# CNC_v36.net
KiCad netlist of a schematic drawn in EAGLE
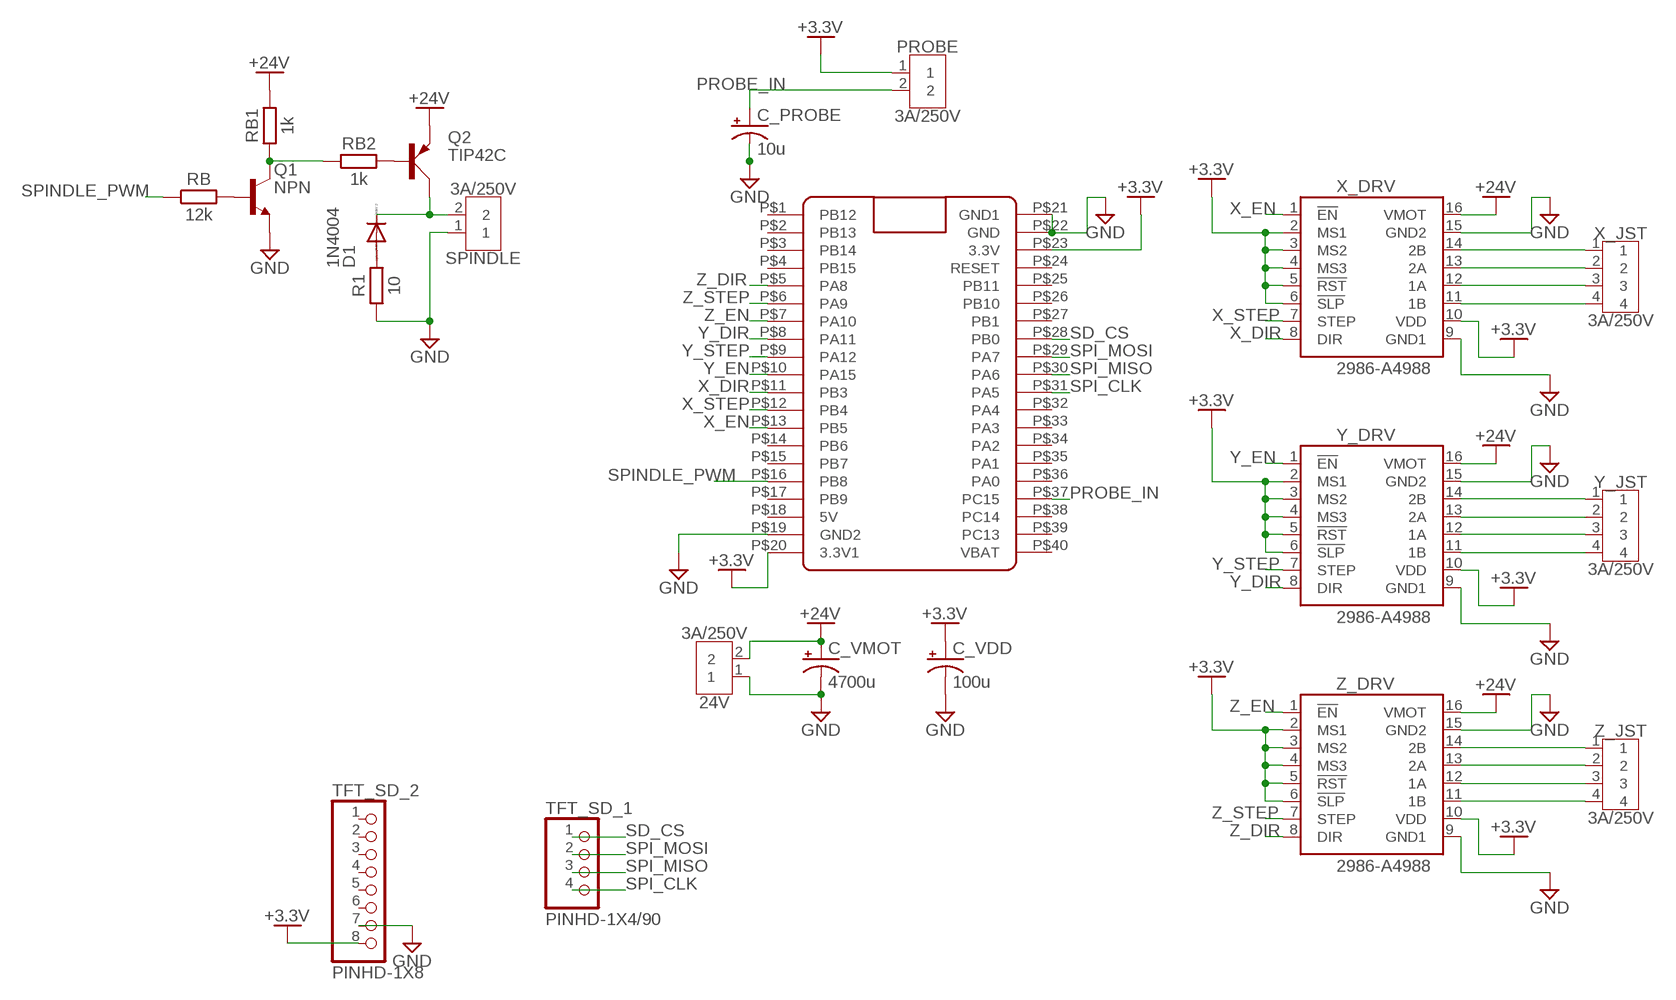
[diagram p0: schematic, sheet 1]

(export (version "E")
  (design (tool "Eeschema 10.0.6"))
  (components
    (comp (ref "24V")
      (value "3A/250V")
      (footprint "eagle-import:B2B-XH-A")
      (fields (field (name "MANUFACTURER") "JST (XH CONNECTOR)") (field (name "MPN") "B2B-XH-A"))
      (libsource (lib "eagle-import") (part "B2B-XH-A"))
    )
    (comp (ref "C_PROBE")
      (value "10u")
      (footprint "eagle-import:CAPPRD508W65D1000H1100B")
      (libsource (lib "eagle-import") (part "C-POL-USRADIAL-11MM-DIA_"))
    )
    (comp (ref "C_VDD")
      (value "100u")
      (footprint "eagle-import:CAPPRD508W65D1000H1100B")
      (libsource (lib "eagle-import") (part "C-POL-USRADIAL-11MM-DIA_"))
    )
    (comp (ref "C_VMOT")
      (value "4700u")
      (footprint "eagle-import:CAPPRD550W60D1200H2000B")
      (libsource (lib "eagle-import") (part "C-POL-USRADIAL-20MM-DIA_"))
    )
    (comp (ref "D1")
      (value "1N4004")
      (footprint "eagle-import:DO41-10")
      (libsource (lib "eagle-import") (part "1N4004"))
    )
    (comp (ref "PROBE")
      (value "3A/250V")
      (footprint "eagle-import:B2B-XH-A")
      (fields (field (name "MANUFACTURER") "JST (XH CONNECTOR)") (field (name "MPN") "B2B-XH-A"))
      (libsource (lib "eagle-import") (part "B2B-XH-A"))
    )
    (comp (ref "Q1")
      (value "NPN")
      (footprint "eagle-import:TO92")
      (libsource (lib "eagle-import") (part "NPNTO92-EBC_"))
    )
    (comp (ref "Q2")
      (value "TIP42C")
      (footprint "eagle-import:TO220AV")
      (fields (field (name "MF") "onsemi"))
      (libsource (lib "eagle-import") (part "TIP42C"))
    )
    (comp (ref "R1")
      (value "10")
      (footprint "eagle-import:RESAD724W46L381D178B")
      (libsource (lib "eagle-import") (part "RAXIAL-7.2MM-PITCH_"))
    )
    (comp (ref "RB")
      (value "12k")
      (footprint "eagle-import:RESAD724W46L381D178B")
      (libsource (lib "eagle-import") (part "RAXIAL-7.2MM-PITCH_"))
    )
    (comp (ref "RB1")
      (value "1k")
      (footprint "eagle-import:RESAD724W46L381D178B")
      (libsource (lib "eagle-import") (part "RAXIAL-7.2MM-PITCH_"))
    )
    (comp (ref "RB2")
      (value "1k")
      (footprint "eagle-import:RESAD724W46L381D178B")
      (libsource (lib "eagle-import") (part "RAXIAL-7.2MM-PITCH_"))
    )
    (comp (ref "SPINDLE")
      (value "3A/250V")
      (footprint "eagle-import:B2B-XH-A")
      (fields (field (name "MANUFACTURER") "JST (XH CONNECTOR)") (field (name "MPN") "B2B-XH-A"))
      (libsource (lib "eagle-import") (part "B2B-XH-A"))
    )
    (comp (ref "TFT_SD_1")
      (value "PINHD-1X4/90")
      (footprint "eagle-import:1X04_90")
      (libsource (lib "eagle-import") (part "PINHD-1X4/90"))
    )
    (comp (ref "TFT_SD_2")
      (value "PINHD-1X8")
      (footprint "eagle-import:1X08")
      (libsource (lib "eagle-import") (part "PINHD-1X8"))
    )
    (comp (ref "U$1")
      (value "BLUE_PILLADVANCED")
      (footprint "eagle-import:BLUE_PILL_ADV")
      (libsource (lib "eagle-import") (part "BLUE_PILLADVANCED"))
    )
    (comp (ref "X_DRV")
      (value "2986-A4988")
      (footprint "eagle-import:A4988")
      (libsource (lib "eagle-import") (part "2986-A4988"))
    )
    (comp (ref "X_JST")
      (value "3A/250V")
      (footprint "eagle-import:B4B-XH-A")
      (fields (field (name "MANUFACTURER") "JST (XH connector)") (field (name "MPN") "B4B-XH-A"))
      (libsource (lib "eagle-import") (part "B4B-XH-A"))
    )
    (comp (ref "Y_DRV")
      (value "2986-A4988")
      (footprint "eagle-import:A4988")
      (libsource (lib "eagle-import") (part "2986-A4988"))
    )
    (comp (ref "Y_JST")
      (value "3A/250V")
      (footprint "eagle-import:B4B-XH-A")
      (fields (field (name "MANUFACTURER") "JST (XH connector)") (field (name "MPN") "B4B-XH-A"))
      (libsource (lib "eagle-import") (part "B4B-XH-A"))
    )
    (comp (ref "Z_DRV")
      (value "2986-A4988")
      (footprint "eagle-import:A4988")
      (libsource (lib "eagle-import") (part "2986-A4988"))
    )
    (comp (ref "Z_JST")
      (value "3A/250V")
      (footprint "eagle-import:B4B-XH-A")
      (fields (field (name "MANUFACTURER") "JST (XH connector)") (field (name "MPN") "B4B-XH-A"))
      (libsource (lib "eagle-import") (part "B4B-XH-A"))
    )
  )
  (nets
    (net (code "1") (name "+3.3V") (class "Default")
      (node (ref "C_VDD") (pin "1") (pinfunction "+_1") (pintype "passive"))
      (node (ref "PROBE") (pin "1") (pinfunction "1_1") (pintype "bidirectional"))
      (node (ref "TFT_SD_2") (pin "8") (pinfunction "8_8") (pintype "passive"))
      (node (ref "U$1") (pin "P$20") (pinfunction "3.3V1_P$20") (pintype "bidirectional"))
      (node (ref "U$1") (pin "P$23") (pinfunction "3.3V_P$23") (pintype "bidirectional"))
      (node (ref "X_DRV") (pin "10") (pinfunction "VDD_10") (pintype "power_in"))
      (node (ref "X_DRV") (pin "2") (pinfunction "MS1_2") (pintype "passive"))
      (node (ref "X_DRV") (pin "3") (pinfunction "MS2_3") (pintype "passive"))
      (node (ref "X_DRV") (pin "4") (pinfunction "MS3_4") (pintype "passive"))
      (node (ref "X_DRV") (pin "5") (pinfunction "~{RST}_5") (pintype "passive"))
      (node (ref "X_DRV") (pin "6") (pinfunction "~{SLP}_6") (pintype "passive"))
      (node (ref "Y_DRV") (pin "10") (pinfunction "VDD_10") (pintype "power_in"))
      (node (ref "Y_DRV") (pin "2") (pinfunction "MS1_2") (pintype "passive"))
      (node (ref "Y_DRV") (pin "3") (pinfunction "MS2_3") (pintype "passive"))
      (node (ref "Y_DRV") (pin "4") (pinfunction "MS3_4") (pintype "passive"))
      (node (ref "Y_DRV") (pin "5") (pinfunction "~{RST}_5") (pintype "passive"))
      (node (ref "Y_DRV") (pin "6") (pinfunction "~{SLP}_6") (pintype "passive"))
      (node (ref "Z_DRV") (pin "10") (pinfunction "VDD_10") (pintype "power_in"))
      (node (ref "Z_DRV") (pin "2") (pinfunction "MS1_2") (pintype "passive"))
      (node (ref "Z_DRV") (pin "3") (pinfunction "MS2_3") (pintype "passive"))
      (node (ref "Z_DRV") (pin "4") (pinfunction "MS3_4") (pintype "passive"))
      (node (ref "Z_DRV") (pin "5") (pinfunction "~{RST}_5") (pintype "passive"))
      (node (ref "Z_DRV") (pin "6") (pinfunction "~{SLP}_6") (pintype "passive"))
    )
    (net (code "2") (name "+24V") (class "Default")
      (node (ref "24V") (pin "2") (pinfunction "2_2") (pintype "bidirectional"))
      (node (ref "C_VMOT") (pin "1") (pinfunction "+_1") (pintype "passive"))
      (node (ref "Q2") (pin "E") (pinfunction "E_E") (pintype "passive"))
      (node (ref "RB1") (pin "2") (pinfunction "2_2") (pintype "passive"))
      (node (ref "X_DRV") (pin "16") (pinfunction "VMOT_16") (pintype "power_in"))
      (node (ref "Y_DRV") (pin "16") (pinfunction "VMOT_16") (pintype "power_in"))
      (node (ref "Z_DRV") (pin "16") (pinfunction "VMOT_16") (pintype "power_in"))
    )
    (net (code "3") (name "/PROBE_IN") (class "Default")
      (node (ref "C_PROBE") (pin "1") (pinfunction "+_1") (pintype "passive"))
      (node (ref "PROBE") (pin "2") (pinfunction "2_2") (pintype "bidirectional"))
      (node (ref "U$1") (pin "P$37") (pinfunction "PC15_P$37") (pintype "bidirectional"))
    )
    (net (code "4") (name "/SD_CS") (class "Default")
      (node (ref "TFT_SD_1") (pin "1") (pinfunction "1_1") (pintype "passive"))
      (node (ref "U$1") (pin "P$28") (pinfunction "PB0_P$28") (pintype "bidirectional"))
    )
    (net (code "5") (name "/SPINDLE_PWM") (class "Default")
      (node (ref "RB") (pin "1") (pinfunction "1_1") (pintype "passive"))
      (node (ref "U$1") (pin "P$16") (pinfunction "PB8_P$16") (pintype "bidirectional"))
    )
    (net (code "6") (name "/SPI_CLK") (class "Default")
      (node (ref "TFT_SD_1") (pin "4") (pinfunction "4_4") (pintype "passive"))
      (node (ref "U$1") (pin "P$31") (pinfunction "PA5_P$31") (pintype "bidirectional"))
    )
    (net (code "7") (name "/SPI_MISO") (class "Default")
      (node (ref "TFT_SD_1") (pin "3") (pinfunction "3_3") (pintype "passive"))
      (node (ref "U$1") (pin "P$30") (pinfunction "PA6_P$30") (pintype "bidirectional"))
    )
    (net (code "8") (name "/SPI_MOSI") (class "Default")
      (node (ref "TFT_SD_1") (pin "2") (pinfunction "2_2") (pintype "passive"))
      (node (ref "U$1") (pin "P$29") (pinfunction "PA7_P$29") (pintype "bidirectional"))
    )
    (net (code "9") (name "/X_DIR") (class "Default")
      (node (ref "U$1") (pin "P$11") (pinfunction "PB3_P$11") (pintype "bidirectional"))
      (node (ref "X_DRV") (pin "8") (pinfunction "DIR_8") (pintype "input"))
    )
    (net (code "10") (name "/X_EN") (class "Default")
      (node (ref "U$1") (pin "P$13") (pinfunction "PB5_P$13") (pintype "bidirectional"))
      (node (ref "X_DRV") (pin "1") (pinfunction "~{EN}_1") (pintype "passive"))
    )
    (net (code "11") (name "/X_STEP") (class "Default")
      (node (ref "U$1") (pin "P$12") (pinfunction "PB4_P$12") (pintype "bidirectional"))
      (node (ref "X_DRV") (pin "7") (pinfunction "STEP_7") (pintype "input"))
    )
    (net (code "12") (name "/Y_DIR") (class "Default")
      (node (ref "U$1") (pin "P$8") (pinfunction "PA11_P$8") (pintype "bidirectional"))
      (node (ref "Y_DRV") (pin "8") (pinfunction "DIR_8") (pintype "input"))
    )
    (net (code "13") (name "/Y_EN") (class "Default")
      (node (ref "U$1") (pin "P$10") (pinfunction "PA15_P$10") (pintype "bidirectional"))
      (node (ref "Y_DRV") (pin "1") (pinfunction "~{EN}_1") (pintype "passive"))
    )
    (net (code "14") (name "/Y_STEP") (class "Default")
      (node (ref "U$1") (pin "P$9") (pinfunction "PA12_P$9") (pintype "bidirectional"))
      (node (ref "Y_DRV") (pin "7") (pinfunction "STEP_7") (pintype "input"))
    )
    (net (code "15") (name "/Z_DIR") (class "Default")
      (node (ref "U$1") (pin "P$5") (pinfunction "PA8_P$5") (pintype "bidirectional"))
      (node (ref "Z_DRV") (pin "8") (pinfunction "DIR_8") (pintype "input"))
    )
    (net (code "16") (name "/Z_EN") (class "Default")
      (node (ref "U$1") (pin "P$7") (pinfunction "PA10_P$7") (pintype "bidirectional"))
      (node (ref "Z_DRV") (pin "1") (pinfunction "~{EN}_1") (pintype "passive"))
    )
    (net (code "17") (name "/Z_STEP") (class "Default")
      (node (ref "U$1") (pin "P$6") (pinfunction "PA9_P$6") (pintype "bidirectional"))
      (node (ref "Z_DRV") (pin "7") (pinfunction "STEP_7") (pintype "input"))
    )
    (net (code "18") (name "GND") (class "Default")
      (node (ref "24V") (pin "1") (pinfunction "1_1") (pintype "bidirectional"))
      (node (ref "C_PROBE") (pin "2") (pinfunction "-_2") (pintype "passive"))
      (node (ref "C_VDD") (pin "2") (pinfunction "-_2") (pintype "passive"))
      (node (ref "C_VMOT") (pin "2") (pinfunction "-_2") (pintype "passive"))
      (node (ref "Q1") (pin "1") (pinfunction "E_1") (pintype "passive"))
      (node (ref "R1") (pin "1") (pinfunction "1_1") (pintype "passive"))
      (node (ref "SPINDLE") (pin "1") (pinfunction "1_1") (pintype "bidirectional"))
      (node (ref "TFT_SD_2") (pin "7") (pinfunction "7_7") (pintype "passive"))
      (node (ref "U$1") (pin "P$19") (pinfunction "GND2_P$19") (pintype "bidirectional"))
      (node (ref "U$1") (pin "P$21") (pinfunction "GND1_P$21") (pintype "power_in"))
      (node (ref "U$1") (pin "P$22") (pinfunction "GND_P$22") (pintype "bidirectional"))
      (node (ref "X_DRV") (pin "15") (pinfunction "GND2_15") (pintype "power_in"))
      (node (ref "X_DRV") (pin "9") (pinfunction "GND1_9") (pintype "power_in"))
      (node (ref "Y_DRV") (pin "15") (pinfunction "GND2_15") (pintype "power_in"))
      (node (ref "Y_DRV") (pin "9") (pinfunction "GND1_9") (pintype "power_in"))
      (node (ref "Z_DRV") (pin "15") (pinfunction "GND2_15") (pintype "power_in"))
      (node (ref "Z_DRV") (pin "9") (pinfunction "GND1_9") (pintype "power_in"))
    )
    (net (code "19") (name "Net-(D1-PadA)") (class "Default")
      (node (ref "D1") (pin "A") (pinfunction "A_A") (pintype "passive"))
      (node (ref "R1") (pin "2") (pinfunction "2_2") (pintype "passive"))
    )
    (net (code "20") (name "Net-(D1-PadC)") (class "Default")
      (node (ref "D1") (pin "C") (pinfunction "C_C") (pintype "passive"))
      (node (ref "Q2") (pin "C") (pinfunction "C_C") (pintype "passive"))
      (node (ref "SPINDLE") (pin "2") (pinfunction "2_2") (pintype "bidirectional"))
    )
    (net (code "21") (name "Net-(Q1-B)") (class "Default")
      (node (ref "Q1") (pin "2") (pinfunction "B_2") (pintype "passive"))
      (node (ref "RB") (pin "2") (pinfunction "2_2") (pintype "passive"))
    )
    (net (code "22") (name "Net-(Q1-C)") (class "Default")
      (node (ref "Q1") (pin "3") (pinfunction "C_3") (pintype "passive"))
      (node (ref "RB1") (pin "1") (pinfunction "1_1") (pintype "passive"))
      (node (ref "RB2") (pin "1") (pinfunction "1_1") (pintype "passive"))
    )
    (net (code "23") (name "Net-(Q2-PadB)") (class "Default")
      (node (ref "Q2") (pin "B") (pinfunction "B_B") (pintype "passive"))
      (node (ref "RB2") (pin "2") (pinfunction "2_2") (pintype "passive"))
    )
    (net (code "24") (name "Net-(X_DRV-1A)") (class "Default")
      (node (ref "X_DRV") (pin "12") (pinfunction "1A_12") (pintype "output"))
      (node (ref "X_JST") (pin "3") (pinfunction "3_3") (pintype "bidirectional"))
    )
    (net (code "25") (name "Net-(X_DRV-1B)") (class "Default")
      (node (ref "X_DRV") (pin "11") (pinfunction "1B_11") (pintype "output"))
      (node (ref "X_JST") (pin "4") (pinfunction "4_4") (pintype "bidirectional"))
    )
    (net (code "26") (name "Net-(X_DRV-2A)") (class "Default")
      (node (ref "X_DRV") (pin "13") (pinfunction "2A_13") (pintype "output"))
      (node (ref "X_JST") (pin "2") (pinfunction "2_2") (pintype "bidirectional"))
    )
    (net (code "27") (name "Net-(X_DRV-2B)") (class "Default")
      (node (ref "X_DRV") (pin "14") (pinfunction "2B_14") (pintype "output"))
      (node (ref "X_JST") (pin "1") (pinfunction "1_1") (pintype "bidirectional"))
    )
    (net (code "28") (name "Net-(Y_DRV-1A)") (class "Default")
      (node (ref "Y_DRV") (pin "12") (pinfunction "1A_12") (pintype "output"))
      (node (ref "Y_JST") (pin "3") (pinfunction "3_3") (pintype "bidirectional"))
    )
    (net (code "29") (name "Net-(Y_DRV-1B)") (class "Default")
      (node (ref "Y_DRV") (pin "11") (pinfunction "1B_11") (pintype "output"))
      (node (ref "Y_JST") (pin "4") (pinfunction "4_4") (pintype "bidirectional"))
    )
    (net (code "30") (name "Net-(Y_DRV-2A)") (class "Default")
      (node (ref "Y_DRV") (pin "13") (pinfunction "2A_13") (pintype "output"))
      (node (ref "Y_JST") (pin "2") (pinfunction "2_2") (pintype "bidirectional"))
    )
    (net (code "31") (name "Net-(Y_DRV-2B)") (class "Default")
      (node (ref "Y_DRV") (pin "14") (pinfunction "2B_14") (pintype "output"))
      (node (ref "Y_JST") (pin "1") (pinfunction "1_1") (pintype "bidirectional"))
    )
    (net (code "32") (name "Net-(Z_DRV-1A)") (class "Default")
      (node (ref "Z_DRV") (pin "12") (pinfunction "1A_12") (pintype "output"))
      (node (ref "Z_JST") (pin "3") (pinfunction "3_3") (pintype "bidirectional"))
    )
    (net (code "33") (name "Net-(Z_DRV-1B)") (class "Default")
      (node (ref "Z_DRV") (pin "11") (pinfunction "1B_11") (pintype "output"))
      (node (ref "Z_JST") (pin "4") (pinfunction "4_4") (pintype "bidirectional"))
    )
    (net (code "34") (name "Net-(Z_DRV-2A)") (class "Default")
      (node (ref "Z_DRV") (pin "13") (pinfunction "2A_13") (pintype "output"))
      (node (ref "Z_JST") (pin "2") (pinfunction "2_2") (pintype "bidirectional"))
    )
    (net (code "35") (name "Net-(Z_DRV-2B)") (class "Default")
      (node (ref "Z_DRV") (pin "14") (pinfunction "2B_14") (pintype "output"))
      (node (ref "Z_JST") (pin "1") (pinfunction "1_1") (pintype "bidirectional"))
    )
    (net (code "36") (name "unconnected-(TFT_SD_2-Pad1)") (class "Default")
      (node (ref "TFT_SD_2") (pin "1") (pinfunction "1_1") (pintype "passive"))
    )
    (net (code "37") (name "unconnected-(TFT_SD_2-Pad2)") (class "Default")
      (node (ref "TFT_SD_2") (pin "2") (pinfunction "2_2") (pintype "passive"))
    )
    (net (code "38") (name "unconnected-(TFT_SD_2-Pad3)") (class "Default")
      (node (ref "TFT_SD_2") (pin "3") (pinfunction "3_3") (pintype "passive"))
    )
    (net (code "39") (name "unconnected-(TFT_SD_2-Pad4)") (class "Default")
      (node (ref "TFT_SD_2") (pin "4") (pinfunction "4_4") (pintype "passive"))
    )
    (net (code "40") (name "unconnected-(TFT_SD_2-Pad5)") (class "Default")
      (node (ref "TFT_SD_2") (pin "5") (pinfunction "5_5") (pintype "passive"))
    )
    (net (code "41") (name "unconnected-(TFT_SD_2-Pad6)") (class "Default")
      (node (ref "TFT_SD_2") (pin "6") (pinfunction "6_6") (pintype "passive"))
    )
    (net (code "42") (name "unconnected-(U$1-5V-PadP$18)") (class "Default")
      (node (ref "U$1") (pin "P$18") (pinfunction "5V_P$18") (pintype "bidirectional"))
    )
    (net (code "43") (name "unconnected-(U$1-PA0-PadP$36)") (class "Default")
      (node (ref "U$1") (pin "P$36") (pinfunction "PA0_P$36") (pintype "bidirectional"))
    )
    (net (code "44") (name "unconnected-(U$1-PA1-PadP$35)") (class "Default")
      (node (ref "U$1") (pin "P$35") (pinfunction "PA1_P$35") (pintype "bidirectional"))
    )
    (net (code "45") (name "unconnected-(U$1-PA2-PadP$34)") (class "Default")
      (node (ref "U$1") (pin "P$34") (pinfunction "PA2_P$34") (pintype "bidirectional"))
    )
    (net (code "46") (name "unconnected-(U$1-PA3-PadP$33)") (class "Default")
      (node (ref "U$1") (pin "P$33") (pinfunction "PA3_P$33") (pintype "bidirectional"))
    )
    (net (code "47") (name "unconnected-(U$1-PA4-PadP$32)") (class "Default")
      (node (ref "U$1") (pin "P$32") (pinfunction "PA4_P$32") (pintype "bidirectional"))
    )
    (net (code "48") (name "unconnected-(U$1-PB1-PadP$27)") (class "Default")
      (node (ref "U$1") (pin "P$27") (pinfunction "PB1_P$27") (pintype "bidirectional"))
    )
    (net (code "49") (name "unconnected-(U$1-PB6-PadP$14)") (class "Default")
      (node (ref "U$1") (pin "P$14") (pinfunction "PB6_P$14") (pintype "bidirectional"))
    )
    (net (code "50") (name "unconnected-(U$1-PB7-PadP$15)") (class "Default")
      (node (ref "U$1") (pin "P$15") (pinfunction "PB7_P$15") (pintype "bidirectional"))
    )
    (net (code "51") (name "unconnected-(U$1-PB9-PadP$17)") (class "Default")
      (node (ref "U$1") (pin "P$17") (pinfunction "PB9_P$17") (pintype "bidirectional"))
    )
    (net (code "52") (name "unconnected-(U$1-PB10-PadP$26)") (class "Default")
      (node (ref "U$1") (pin "P$26") (pinfunction "PB10_P$26") (pintype "bidirectional"))
    )
    (net (code "53") (name "unconnected-(U$1-PB11-PadP$25)") (class "Default")
      (node (ref "U$1") (pin "P$25") (pinfunction "PB11_P$25") (pintype "bidirectional"))
    )
    (net (code "54") (name "unconnected-(U$1-PB12-PadP$1)") (class "Default")
      (node (ref "U$1") (pin "P$1") (pinfunction "PB12_P$1") (pintype "bidirectional"))
    )
    (net (code "55") (name "unconnected-(U$1-PB13-PadP$2)") (class "Default")
      (node (ref "U$1") (pin "P$2") (pinfunction "PB13_P$2") (pintype "bidirectional"))
    )
    (net (code "56") (name "unconnected-(U$1-PB14-PadP$3)") (class "Default")
      (node (ref "U$1") (pin "P$3") (pinfunction "PB14_P$3") (pintype "bidirectional"))
    )
    (net (code "57") (name "unconnected-(U$1-PB15-PadP$4)") (class "Default")
      (node (ref "U$1") (pin "P$4") (pinfunction "PB15_P$4") (pintype "bidirectional"))
    )
    (net (code "58") (name "unconnected-(U$1-PC13-PadP$39)") (class "Default")
      (node (ref "U$1") (pin "P$39") (pinfunction "PC13_P$39") (pintype "bidirectional"))
    )
    (net (code "59") (name "unconnected-(U$1-PC14-PadP$38)") (class "Default")
      (node (ref "U$1") (pin "P$38") (pinfunction "PC14_P$38") (pintype "bidirectional"))
    )
    (net (code "60") (name "unconnected-(U$1-RESET-PadP$24)") (class "Default")
      (node (ref "U$1") (pin "P$24") (pinfunction "RESET_P$24") (pintype "bidirectional"))
    )
    (net (code "61") (name "unconnected-(U$1-VBAT-PadP$40)") (class "Default")
      (node (ref "U$1") (pin "P$40") (pinfunction "VBAT_P$40") (pintype "bidirectional"))
    )
  )
)
